# 05_-_EEPROM-RTC-LCD.net
KiCad netlist of a schematic drawn in Altium Designer
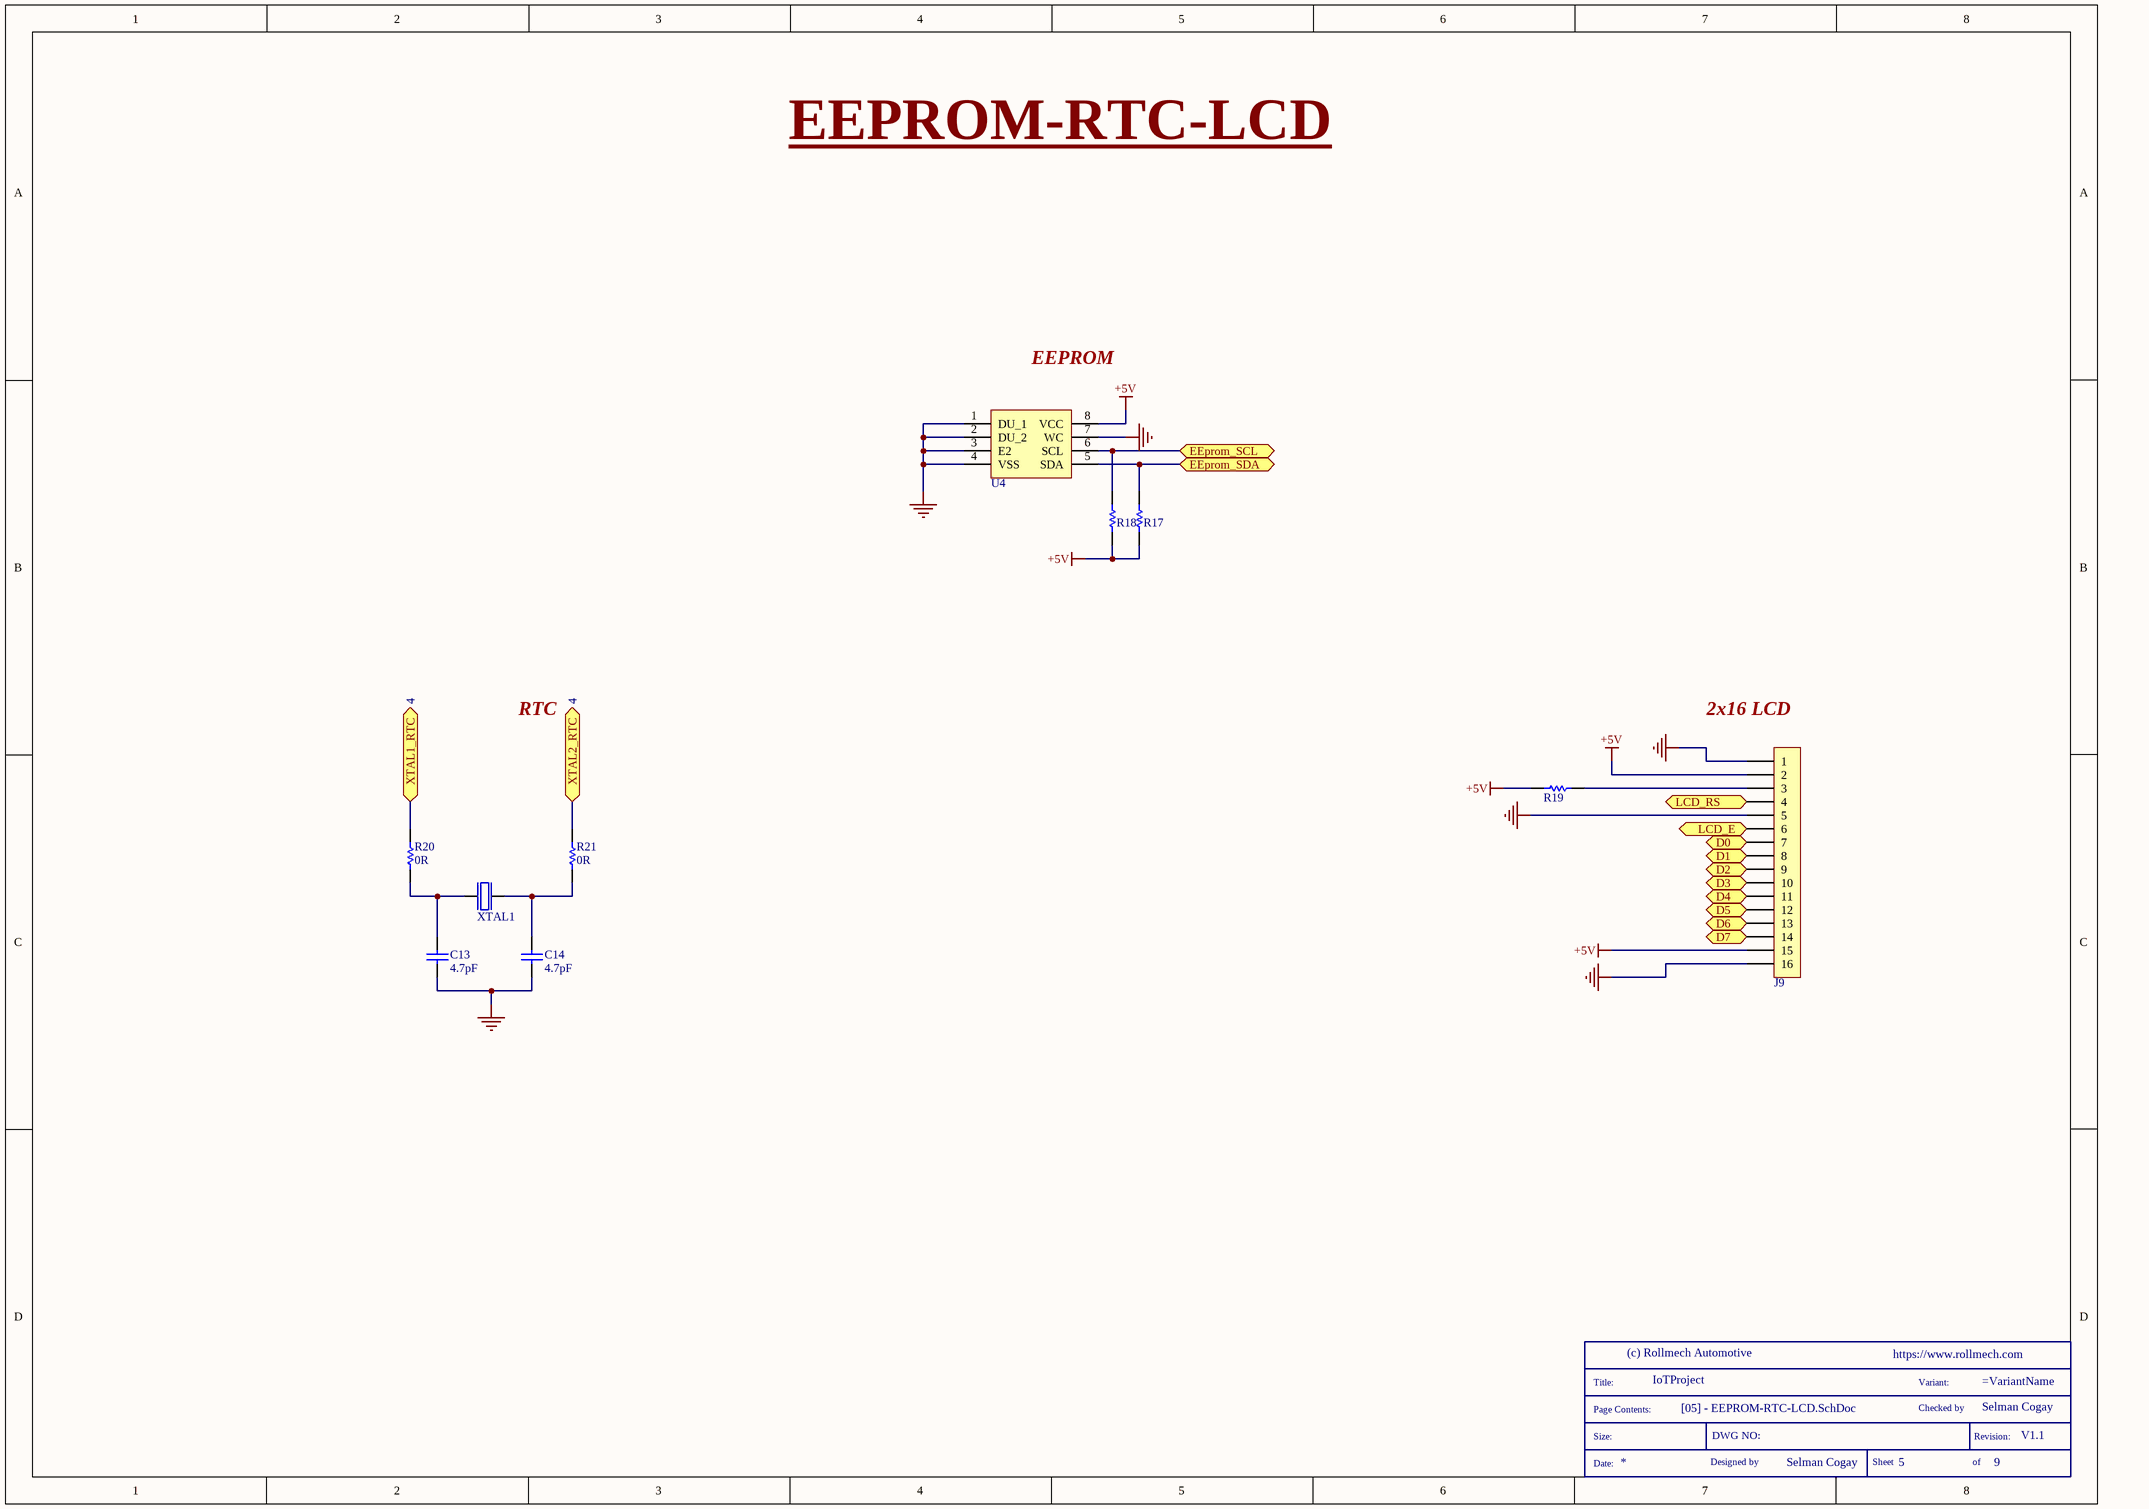
[diagram p0: [05] - EEPROM-RTC-LCD.SchDoc]

(export (version "E")
  (design (tool "Eeschema 10.0.6"))
  (components
    (comp (ref "C13")
      (value "4.7pF")
      (footprint "C0603")
      (description "CAP CER 4.7PF 50V C0G 0603")
      (libsource (lib "SN65HVD2xx-CAN-Module-V1I1") (part "CGA3E2C0G1H4R7C080AA"))
    )
    (comp (ref "C14")
      (value "4.7pF")
      (footprint "C0603")
      (description "CAP CER 4.7PF 50V C0G 0603")
      (libsource (lib "SN65HVD2xx-CAN-Module-V1I1") (part "CGA3E2C0G1H4R7C080AA"))
    )
    (comp (ref "J9")
      (value "HDR FEMALE 1x16 2.54MM")
      (footprint "HDR_FEMALE_1x16_2.54MM")
      (libsource (lib "Rollmech_Altium") (part "PPTC161LFBN-RC"))
    )
    (comp (ref "R17")
      (value "5.6k 1/8W")
      (footprint "RES_0805")
      (description "RES SMD 5.6K OHM 1% 1/8W 0805")
      (libsource (lib "Rollmech_Altium") (part "ERJ-6ENF5601V"))
    )
    (comp (ref "R18")
      (value "5.6k 1/8W")
      (footprint "RES_0805")
      (description "RES SMD 5.6K OHM 1% 1/8W 0805")
      (libsource (lib "Rollmech_Altium") (part "ERJ-6ENF5601V"))
    )
    (comp (ref "R19")
      (value "1K 1/8W")
      (footprint "RES_0805")
      (description "RES SMD 1K OHM")
      (libsource (lib "Rollmech_Altium") (part "ERJ-6ENF1001V"))
    )
    (comp (ref "R20")
      (value "0R")
      (footprint "R0805")
      (description "RES SMD 0 OHM JUMPER 1/8W 0805")
      (libsource (lib "SN65HVD2xx-CAN-Module-V1I1") (part "CRCW08050000Z0EA"))
    )
    (comp (ref "R21")
      (value "0R")
      (footprint "R0805")
      (description "RES SMD 0 OHM JUMPER 1/8W 0805")
      (libsource (lib "SN65HVD2xx-CAN-Module-V1I1") (part "CRCW08050000Z0EA"))
    )
    (comp (ref "U4")
      (value "2M EEPROM")
      (footprint "SOIC-8")
      (description "IC EEPROM 2M I2C 1MHZ 8SO")
      (libsource (lib "Rollmech_Altium") (part "M24M02-DWMN3TP/K"))
    )
    (comp (ref "XTAL1")
      (value "32.768KHZ")
      (footprint "XTAL_2SMD")
      (description "CRYSTAL 32.768KHZ")
      (libsource (lib "Rollmech_Altium") (part "ECS-.327-6-34QCS-TR"))
    )
  )
  (nets
    (net (code "1") (name "+5V") (class "Default")
      (node (ref "J9") (pin "15") (pinfunction "15_15") (pintype "passive"))
      (node (ref "J9") (pin "2") (pinfunction "2_2") (pintype "passive"))
      (node (ref "R17") (pin "1") (pinfunction "1_1") (pintype "passive"))
      (node (ref "R18") (pin "1") (pinfunction "1_1") (pintype "passive"))
      (node (ref "R19") (pin "1") (pinfunction "1_1") (pintype "passive"))
      (node (ref "U4") (pin "8") (pinfunction "VCC_8") (pintype "passive"))
    )
    (net (code "2") (name "/D0") (class "Default")
      (node (ref "J9") (pin "7") (pinfunction "7_7") (pintype "passive"))
    )
    (net (code "3") (name "/D1") (class "Default")
      (node (ref "J9") (pin "8") (pinfunction "8_8") (pintype "passive"))
    )
    (net (code "4") (name "/D2") (class "Default")
      (node (ref "J9") (pin "9") (pinfunction "9_9") (pintype "passive"))
    )
    (net (code "5") (name "/D3") (class "Default")
      (node (ref "J9") (pin "10") (pinfunction "10_10") (pintype "passive"))
    )
    (net (code "6") (name "/D4") (class "Default")
      (node (ref "J9") (pin "11") (pinfunction "11_11") (pintype "passive"))
    )
    (net (code "7") (name "/D5") (class "Default")
      (node (ref "J9") (pin "12") (pinfunction "12_12") (pintype "passive"))
    )
    (net (code "8") (name "/D6") (class "Default")
      (node (ref "J9") (pin "13") (pinfunction "13_13") (pintype "passive"))
    )
    (net (code "9") (name "/D7") (class "Default")
      (node (ref "J9") (pin "14") (pinfunction "14_14") (pintype "passive"))
    )
    (net (code "10") (name "/EEprom_SCL") (class "Default")
      (node (ref "R18") (pin "2") (pinfunction "2_2") (pintype "passive"))
      (node (ref "U4") (pin "6") (pinfunction "SCL_6") (pintype "passive"))
    )
    (net (code "11") (name "/EEprom_SDA") (class "Default")
      (node (ref "R17") (pin "2") (pinfunction "2_2") (pintype "passive"))
      (node (ref "U4") (pin "5") (pinfunction "SDA_5") (pintype "passive"))
    )
    (net (code "12") (name "/LCD_E") (class "Default")
      (node (ref "J9") (pin "6") (pinfunction "6_6") (pintype "passive"))
    )
    (net (code "13") (name "/LCD_RS") (class "Default")
      (node (ref "J9") (pin "4") (pinfunction "4_4") (pintype "passive"))
    )
    (net (code "14") (name "/XTAL1_RTC") (class "Default")
      (node (ref "R20") (pin "2") (pinfunction "2_2") (pintype "passive"))
    )
    (net (code "15") (name "/XTAL2_RTC") (class "Default")
      (node (ref "R21") (pin "2") (pinfunction "2_2") (pintype "passive"))
    )
    (net (code "16") (name "GND") (class "Default")
      (node (ref "C13") (pin "1") (pinfunction "1_1") (pintype "passive"))
      (node (ref "C14") (pin "1") (pinfunction "1_1") (pintype "passive"))
      (node (ref "J9") (pin "1") (pinfunction "1_1") (pintype "passive"))
      (node (ref "J9") (pin "16") (pinfunction "16_16") (pintype "passive"))
      (node (ref "J9") (pin "5") (pinfunction "5_5") (pintype "passive"))
      (node (ref "U4") (pin "1") (pinfunction "DU_1_1") (pintype "passive"))
      (node (ref "U4") (pin "2") (pinfunction "DU_2_2") (pintype "passive"))
      (node (ref "U4") (pin "3") (pinfunction "E2_3") (pintype "passive"))
      (node (ref "U4") (pin "4") (pinfunction "VSS_4") (pintype "passive"))
      (node (ref "U4") (pin "7") (pinfunction "WC_7") (pintype "passive"))
    )
    (net (code "17") (name "Net-(C13-Pad2)") (class "Default")
      (node (ref "C13") (pin "2") (pinfunction "2_2") (pintype "passive"))
      (node (ref "R20") (pin "1") (pinfunction "1_1") (pintype "passive"))
      (node (ref "XTAL1") (pin "1") (pinfunction "1_1") (pintype "passive"))
    )
    (net (code "18") (name "Net-(C14-Pad2)") (class "Default")
      (node (ref "C14") (pin "2") (pinfunction "2_2") (pintype "passive"))
      (node (ref "R21") (pin "1") (pinfunction "1_1") (pintype "passive"))
      (node (ref "XTAL1") (pin "2") (pinfunction "2_2") (pintype "passive"))
    )
    (net (code "19") (name "Net-(J9-Pad3)") (class "Default")
      (node (ref "J9") (pin "3") (pinfunction "3_3") (pintype "passive"))
      (node (ref "R19") (pin "2") (pinfunction "2_2") (pintype "passive"))
    )
  )
)
